# IOTBeev0_2.net
KiCad netlist of a schematic drawn in EAGLE
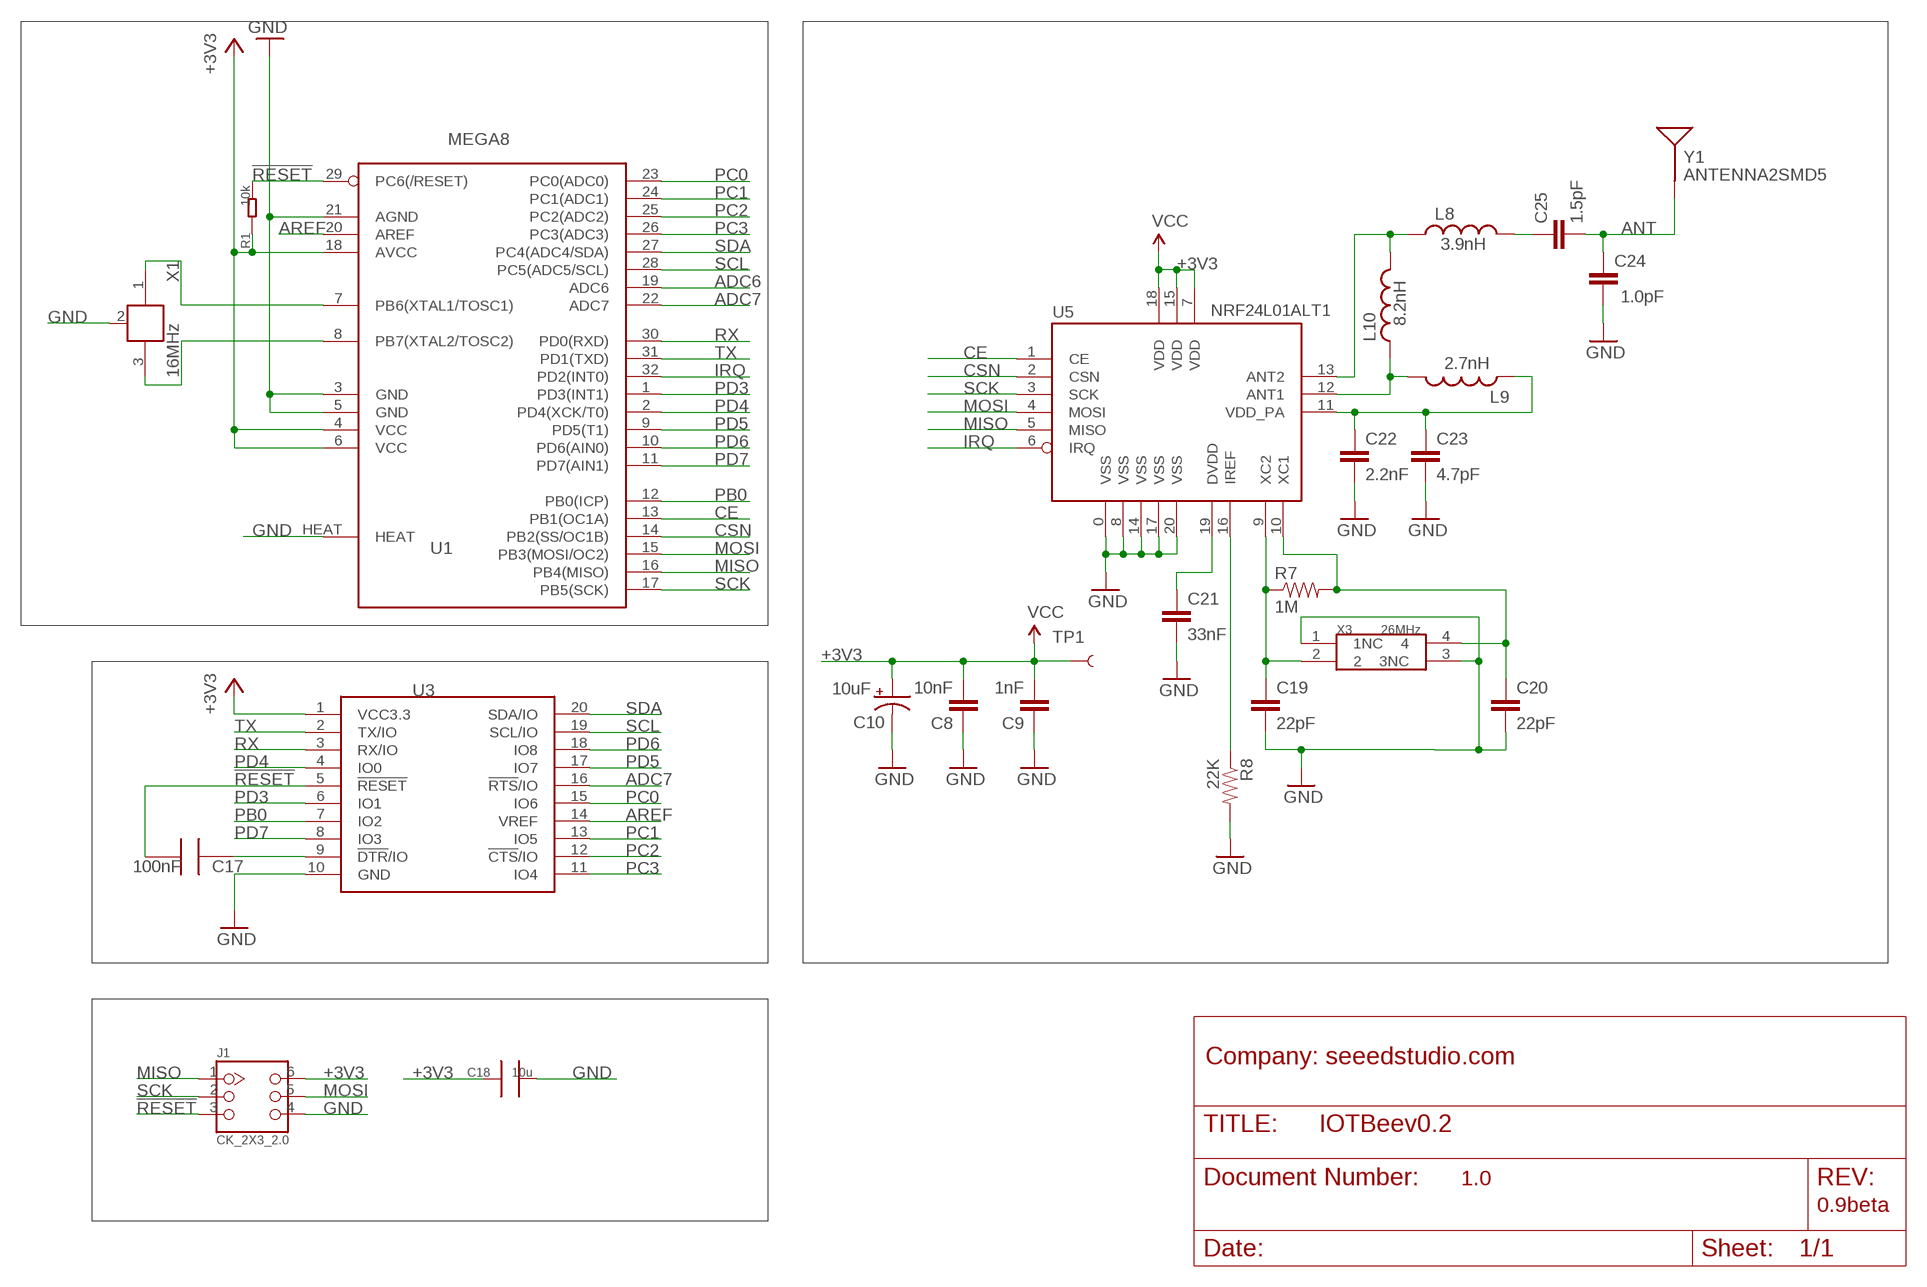
[diagram p0: schematic, sheet 1]

(export (version "E")
  (design (tool "Eeschema 10.0.6"))
  (components
    (comp (ref "C8")
      (value "10nF")
      (footprint "eagle-import:0402-CAP")
      (libsource (lib "eagle-import") (part "CAP0402-CAP"))
    )
    (comp (ref "C9")
      (value "1nF")
      (footprint "eagle-import:0402-CAP")
      (libsource (lib "eagle-import") (part "CAP0402-CAP"))
    )
    (comp (ref "C10")
      (value "10uF")
      (footprint "eagle-import:EIA3528")
      (libsource (lib "eagle-import") (part "CAP_POL3528"))
    )
    (comp (ref "C17")
      (value "100nF")
      (footprint "eagle-import:0603_S")
      (libsource (lib "eagle-import") (part "C0603_S"))
    )
    (comp (ref "C18")
      (value "10u")
      (footprint "eagle-import:0805")
      (libsource (lib "eagle-import") (part "C0805"))
    )
    (comp (ref "C19")
      (value "22pF")
      (footprint "eagle-import:0402-CAP")
      (libsource (lib "eagle-import") (part "CAP0402-CAP"))
    )
    (comp (ref "C20")
      (value "22pF")
      (footprint "eagle-import:0402-CAP")
      (libsource (lib "eagle-import") (part "CAP0402-CAP"))
    )
    (comp (ref "C21")
      (value "33nF")
      (footprint "eagle-import:0402-CAP")
      (libsource (lib "eagle-import") (part "CAP0402-CAP"))
    )
    (comp (ref "C22")
      (value "2.2nF")
      (footprint "eagle-import:0402-CAP")
      (libsource (lib "eagle-import") (part "CAP0402-CAP"))
    )
    (comp (ref "C23")
      (value "4.7pF")
      (footprint "eagle-import:0402-CAP")
      (libsource (lib "eagle-import") (part "CAP0402-CAP"))
    )
    (comp (ref "C24")
      (value "1.0pF")
      (footprint "eagle-import:0402-CAP")
      (libsource (lib "eagle-import") (part "CAP0402-CAP"))
    )
    (comp (ref "C25")
      (value "1.5pF")
      (footprint "eagle-import:0402-CAP")
      (libsource (lib "eagle-import") (part "CAP0402-CAP"))
    )
    (comp (ref "J1")
      (value "CK_2X3_2.0")
      (footprint "eagle-import:CK_2X3_2.0")
      (libsource (lib "eagle-import") (part "CK_2X3_2.0"))
    )
    (comp (ref "L8")
      (value "3.9nH")
      (footprint "eagle-import:C0402")
      (libsource (lib "eagle-import") (part "INDUCTOR0402"))
    )
    (comp (ref "L9")
      (value "2.7nH")
      (footprint "eagle-import:C0402")
      (libsource (lib "eagle-import") (part "INDUCTOR0402"))
    )
    (comp (ref "L10")
      (value "8.2nH")
      (footprint "eagle-import:C0402")
      (libsource (lib "eagle-import") (part "INDUCTOR0402"))
    )
    (comp (ref "R1")
      (value "10k")
      (footprint "eagle-import:0603_S")
      (libsource (lib "eagle-import") (part "R0603_S"))
    )
    (comp (ref "R7")
      (value "1M")
      (footprint "eagle-import:0402-RES")
      (libsource (lib "eagle-import") (part "RESISTOR0402-RES"))
    )
    (comp (ref "R8")
      (value "22K")
      (footprint "eagle-import:0402-RES")
      (libsource (lib "eagle-import") (part "RESISTOR0402-RES"))
    )
    (comp (ref "TP1")
      (value "TEST-POINT3X5")
      (footprint "eagle-import:PAD.03X.05")
      (libsource (lib "eagle-import") (part "TEST-POINT3X5"))
    )
    (comp (ref "U1")
      (value "MEGA8")
      (footprint "eagle-import:MLF32X")
      (libsource (lib "eagle-import") (part "MEGA8"))
    )
    (comp (ref "U3")
      (value "BEE-OPENBEE-BTSMD")
      (footprint "eagle-import:20P-SMD-2.0-BT")
      (libsource (lib "eagle-import") (part "BEE-OPENBEE-BTSMD"))
    )
    (comp (ref "U5")
      (value "NRF24L01ALT1")
      (footprint "eagle-import:QFN20_ALT1")
      (libsource (lib "eagle-import") (part "NRF24L01ALT1"))
    )
    (comp (ref "X1")
      (value "16MHz")
      (footprint "eagle-import:XTAL_3X2")
      (libsource (lib "eagle-import") (part "XTAL_NCVER"))
    )
    (comp (ref "X3")
      (value "26MHz")
      (footprint "eagle-import:X3225")
      (libsource (lib "eagle-import") (part "XTAL_SMD_3225"))
    )
    (comp (ref "Y1")
      (value "ANTENNA2SMD5")
      (footprint "eagle-import:ANTENNA-CHIP5")
      (libsource (lib "eagle-import") (part "ANTENNA2SMD5"))
    )
  )
  (nets
    (net (code "1") (name "+3V3") (class "Default")
      (node (ref "C10") (pin "A") (pinfunction "+_A") (pintype "passive"))
      (node (ref "C18") (pin "1") (pinfunction "1_1") (pintype "bidirectional"))
      (node (ref "C8") (pin "2") (pinfunction "2_2") (pintype "passive"))
      (node (ref "C9") (pin "2") (pinfunction "2_2") (pintype "passive"))
      (node (ref "J1") (pin "6") (pinfunction "P$6_6") (pintype "bidirectional"))
      (node (ref "R1") (pin "1") (pinfunction "1_1") (pintype "bidirectional"))
      (node (ref "TP1") (pin "P$1") (pinfunction "1_P$1") (pintype "bidirectional"))
      (node (ref "U1") (pin "18") (pinfunction "AVCC_18") (pintype "bidirectional"))
      (node (ref "U1") (pin "4") (pinfunction "VCC_4") (pintype "bidirectional"))
      (node (ref "U1") (pin "6") (pinfunction "VCC_6") (pintype "bidirectional"))
      (node (ref "U3") (pin "1") (pinfunction "VCC3.3_1") (pintype "bidirectional"))
      (node (ref "U5") (pin "15") (pinfunction "VDD_15") (pintype "power_in"))
      (node (ref "U5") (pin "18") (pinfunction "VDD_18") (pintype "power_in"))
      (node (ref "U5") (pin "7") (pinfunction "VDD_7") (pintype "power_in"))
    )
    (net (code "2") (name "/ADC6") (class "Default")
      (node (ref "U1") (pin "19") (pinfunction "ADC6_19") (pintype "bidirectional"))
    )
    (net (code "3") (name "/ADC7") (class "Default")
      (node (ref "U1") (pin "22") (pinfunction "ADC7_22") (pintype "bidirectional"))
      (node (ref "U3") (pin "16") (pinfunction "~{RTS}/IO_16") (pintype "bidirectional"))
    )
    (net (code "4") (name "/ANT") (class "Default")
      (node (ref "C24") (pin "2") (pinfunction "2_2") (pintype "passive"))
      (node (ref "C25") (pin "2") (pinfunction "2_2") (pintype "passive"))
      (node (ref "Y1") (pin "FEED") (pinfunction "SIGNAL_FEED") (pintype "bidirectional"))
    )
    (net (code "5") (name "/AREF") (class "Default")
      (node (ref "U1") (pin "20") (pinfunction "AREF_20") (pintype "bidirectional"))
      (node (ref "U3") (pin "14") (pinfunction "VREF_14") (pintype "bidirectional"))
    )
    (net (code "6") (name "/CE") (class "Default")
      (node (ref "U1") (pin "13") (pinfunction "PB1(OC1A)_13") (pintype "bidirectional"))
      (node (ref "U5") (pin "1") (pinfunction "CE_1") (pintype "input"))
    )
    (net (code "7") (name "/CSN") (class "Default")
      (node (ref "U1") (pin "14") (pinfunction "PB2(SS/OC1B)_14") (pintype "bidirectional"))
      (node (ref "U5") (pin "2") (pinfunction "CSN_2") (pintype "input"))
    )
    (net (code "8") (name "/IRQ") (class "Default")
      (node (ref "U1") (pin "32") (pinfunction "PD2(INT0)_32") (pintype "bidirectional"))
      (node (ref "U5") (pin "6") (pinfunction "IRQ_6") (pintype "output"))
    )
    (net (code "9") (name "/MISO") (class "Default")
      (node (ref "J1") (pin "1") (pinfunction "P$1_1") (pintype "bidirectional"))
      (node (ref "U1") (pin "16") (pinfunction "PB4(MISO)_16") (pintype "bidirectional"))
      (node (ref "U5") (pin "5") (pinfunction "MISO_5") (pintype "output"))
    )
    (net (code "10") (name "/MOSI") (class "Default")
      (node (ref "J1") (pin "5") (pinfunction "P$5_5") (pintype "bidirectional"))
      (node (ref "U1") (pin "15") (pinfunction "PB3(MOSI/OC2)_15") (pintype "bidirectional"))
      (node (ref "U5") (pin "4") (pinfunction "MOSI_4") (pintype "input"))
    )
    (net (code "11") (name "/PB0") (class "Default")
      (node (ref "U1") (pin "12") (pinfunction "PB0(ICP)_12") (pintype "bidirectional"))
      (node (ref "U3") (pin "7") (pinfunction "IO2_7") (pintype "bidirectional"))
    )
    (net (code "12") (name "/PC0") (class "Default")
      (node (ref "U1") (pin "23") (pinfunction "PC0(ADC0)_23") (pintype "bidirectional"))
      (node (ref "U3") (pin "15") (pinfunction "IO6_15") (pintype "bidirectional"))
    )
    (net (code "13") (name "/PC1") (class "Default")
      (node (ref "U1") (pin "24") (pinfunction "PC1(ADC1)_24") (pintype "bidirectional"))
      (node (ref "U3") (pin "13") (pinfunction "IO5_13") (pintype "bidirectional"))
    )
    (net (code "14") (name "/PC2") (class "Default")
      (node (ref "U1") (pin "25") (pinfunction "PC2(ADC2)_25") (pintype "bidirectional"))
      (node (ref "U3") (pin "12") (pinfunction "~{CTS}/IO_12") (pintype "bidirectional"))
    )
    (net (code "15") (name "/PC3") (class "Default")
      (node (ref "U1") (pin "26") (pinfunction "PC3(ADC3)_26") (pintype "bidirectional"))
      (node (ref "U3") (pin "11") (pinfunction "IO4_11") (pintype "bidirectional"))
    )
    (net (code "16") (name "/PD3") (class "Default")
      (node (ref "U1") (pin "1") (pinfunction "PD3(INT1)_1") (pintype "bidirectional"))
      (node (ref "U3") (pin "6") (pinfunction "IO1_6") (pintype "bidirectional"))
    )
    (net (code "17") (name "/PD4") (class "Default")
      (node (ref "U1") (pin "2") (pinfunction "PD4(XCK/T0)_2") (pintype "bidirectional"))
      (node (ref "U3") (pin "4") (pinfunction "IO0_4") (pintype "bidirectional"))
    )
    (net (code "18") (name "/PD5") (class "Default")
      (node (ref "U1") (pin "9") (pinfunction "PD5(T1)_9") (pintype "bidirectional"))
      (node (ref "U3") (pin "17") (pinfunction "IO7_17") (pintype "bidirectional"))
    )
    (net (code "19") (name "/PD6") (class "Default")
      (node (ref "U1") (pin "10") (pinfunction "PD6(AIN0)_10") (pintype "bidirectional"))
      (node (ref "U3") (pin "18") (pinfunction "IO8_18") (pintype "bidirectional"))
    )
    (net (code "20") (name "/PD7") (class "Default")
      (node (ref "U1") (pin "11") (pinfunction "PD7(AIN1)_11") (pintype "bidirectional"))
      (node (ref "U3") (pin "8") (pinfunction "IO3_8") (pintype "bidirectional"))
    )
    (net (code "21") (name "/RX") (class "Default")
      (node (ref "U1") (pin "30") (pinfunction "PD0(RXD)_30") (pintype "bidirectional"))
      (node (ref "U3") (pin "3") (pinfunction "RX/IO_3") (pintype "bidirectional"))
    )
    (net (code "22") (name "/SCK") (class "Default")
      (node (ref "J1") (pin "2") (pinfunction "P$2_2") (pintype "bidirectional"))
      (node (ref "U1") (pin "17") (pinfunction "PB5(SCK)_17") (pintype "bidirectional"))
      (node (ref "U5") (pin "3") (pinfunction "SCK_3") (pintype "input"))
    )
    (net (code "23") (name "/SCL") (class "Default")
      (node (ref "U1") (pin "28") (pinfunction "PC5(ADC5/SCL)_28") (pintype "bidirectional"))
      (node (ref "U3") (pin "19") (pinfunction "SCL/IO_19") (pintype "bidirectional"))
    )
    (net (code "24") (name "/SDA") (class "Default")
      (node (ref "U1") (pin "27") (pinfunction "PC4(ADC4/SDA)_27") (pintype "bidirectional"))
      (node (ref "U3") (pin "20") (pinfunction "SDA/IO_20") (pintype "bidirectional"))
    )
    (net (code "25") (name "/TX") (class "Default")
      (node (ref "U1") (pin "31") (pinfunction "PD1(TXD)_31") (pintype "bidirectional"))
      (node (ref "U3") (pin "2") (pinfunction "TX/IO_2") (pintype "bidirectional"))
    )
    (net (code "26") (name "/~{RESET}") (class "Default")
      (node (ref "C17") (pin "2") (pinfunction "2_2") (pintype "bidirectional"))
      (node (ref "J1") (pin "3") (pinfunction "P$3_3") (pintype "bidirectional"))
      (node (ref "R1") (pin "2") (pinfunction "2_2") (pintype "bidirectional"))
      (node (ref "U1") (pin "29") (pinfunction "PC6(/RESET)_29") (pintype "bidirectional"))
      (node (ref "U3") (pin "5") (pinfunction "~{RESET}_5") (pintype "bidirectional"))
    )
    (net (code "27") (name "GND") (class "Default")
      (node (ref "C10") (pin "C") (pinfunction "-_C") (pintype "passive"))
      (node (ref "C18") (pin "2") (pinfunction "2_2") (pintype "bidirectional"))
      (node (ref "C19") (pin "2") (pinfunction "2_2") (pintype "passive"))
      (node (ref "C20") (pin "2") (pinfunction "2_2") (pintype "passive"))
      (node (ref "C21") (pin "2") (pinfunction "2_2") (pintype "passive"))
      (node (ref "C22") (pin "2") (pinfunction "2_2") (pintype "passive"))
      (node (ref "C23") (pin "2") (pinfunction "2_2") (pintype "passive"))
      (node (ref "C24") (pin "1") (pinfunction "1_1") (pintype "passive"))
      (node (ref "C8") (pin "1") (pinfunction "1_1") (pintype "passive"))
      (node (ref "C9") (pin "1") (pinfunction "1_1") (pintype "passive"))
      (node (ref "J1") (pin "4") (pinfunction "P$4_4") (pintype "bidirectional"))
      (node (ref "R8") (pin "2") (pinfunction "2_2") (pintype "passive"))
      (node (ref "U1") (pin "21") (pinfunction "AGND_21") (pintype "bidirectional"))
      (node (ref "U1") (pin "3") (pinfunction "GND_3") (pintype "bidirectional"))
      (node (ref "U1") (pin "5") (pinfunction "GND_5") (pintype "bidirectional"))
      (node (ref "U1") (pin "HEAT") (pinfunction "HEAT_HEAT") (pintype "bidirectional"))
      (node (ref "U3") (pin "10") (pinfunction "GND_10") (pintype "bidirectional"))
      (node (ref "U5") (pin "0") (pinfunction "VSS_0") (pintype "power_in"))
      (node (ref "U5") (pin "14") (pinfunction "VSS_14") (pintype "power_in"))
      (node (ref "U5") (pin "17") (pinfunction "VSS_17") (pintype "power_in"))
      (node (ref "U5") (pin "20") (pinfunction "VSS_20") (pintype "power_in"))
      (node (ref "U5") (pin "8") (pinfunction "VSS_8") (pintype "power_in"))
      (node (ref "X1") (pin "2") (pinfunction "GND_2") (pintype "bidirectional"))
      (node (ref "X3") (pin "1") (pinfunction "1NC_1") (pintype "bidirectional"))
      (node (ref "X3") (pin "3") (pinfunction "3NC_3") (pintype "bidirectional"))
    )
    (net (code "28") (name "Net-(C25-Pad1)") (class "Default")
      (node (ref "C25") (pin "1") (pinfunction "1_1") (pintype "passive"))
      (node (ref "L8") (pin "2") (pinfunction "2_2") (pintype "passive"))
    )
    (net (code "29") (name "Net-(U1-PB6(XTAL1{slash}TOSC1))") (class "Default")
      (node (ref "U1") (pin "7") (pinfunction "PB6(XTAL1/TOSC1)_7") (pintype "bidirectional"))
      (node (ref "X1") (pin "1") (pinfunction "1_1") (pintype "bidirectional"))
    )
    (net (code "30") (name "Net-(U1-PB7(XTAL2{slash}TOSC2))") (class "Default")
      (node (ref "U1") (pin "8") (pinfunction "PB7(XTAL2/TOSC2)_8") (pintype "bidirectional"))
      (node (ref "X1") (pin "3") (pinfunction "2_3") (pintype "bidirectional"))
    )
    (net (code "31") (name "Net-(U3-~{DTR}{slash}IO)") (class "Default")
      (node (ref "C17") (pin "1") (pinfunction "1_1") (pintype "bidirectional"))
      (node (ref "U3") (pin "9") (pinfunction "~{DTR}/IO_9") (pintype "bidirectional"))
    )
    (net (code "32") (name "Net-(U5-ANT1)") (class "Default")
      (node (ref "L10") (pin "1") (pinfunction "1_1") (pintype "passive"))
      (node (ref "L9") (pin "2") (pinfunction "2_2") (pintype "passive"))
      (node (ref "U5") (pin "12") (pinfunction "ANT1_12") (pintype "output"))
    )
    (net (code "33") (name "Net-(U5-ANT2)") (class "Default")
      (node (ref "L10") (pin "2") (pinfunction "2_2") (pintype "passive"))
      (node (ref "L8") (pin "1") (pinfunction "1_1") (pintype "passive"))
      (node (ref "U5") (pin "13") (pinfunction "ANT2_13") (pintype "output"))
    )
    (net (code "34") (name "Net-(U5-DVDD)") (class "Default")
      (node (ref "C21") (pin "1") (pinfunction "1_1") (pintype "passive"))
      (node (ref "U5") (pin "19") (pinfunction "DVDD_19") (pintype "power_in"))
    )
    (net (code "35") (name "Net-(U5-IREF)") (class "Default")
      (node (ref "R8") (pin "1") (pinfunction "1_1") (pintype "passive"))
      (node (ref "U5") (pin "16") (pinfunction "IREF_16") (pintype "input"))
    )
    (net (code "36") (name "Net-(U5-VDD_PA)") (class "Default")
      (node (ref "C22") (pin "1") (pinfunction "1_1") (pintype "passive"))
      (node (ref "C23") (pin "1") (pinfunction "1_1") (pintype "passive"))
      (node (ref "L9") (pin "1") (pinfunction "1_1") (pintype "passive"))
      (node (ref "U5") (pin "11") (pinfunction "VDD_PA_11") (pintype "power_in"))
    )
    (net (code "37") (name "Net-(U5-XC1)") (class "Default")
      (node (ref "C20") (pin "1") (pinfunction "1_1") (pintype "passive"))
      (node (ref "R7") (pin "2") (pinfunction "2_2") (pintype "passive"))
      (node (ref "U5") (pin "10") (pinfunction "XC1_10") (pintype "input"))
      (node (ref "X3") (pin "4") (pinfunction "4_4") (pintype "bidirectional"))
    )
    (net (code "38") (name "Net-(U5-XC2)") (class "Default")
      (node (ref "C19") (pin "1") (pinfunction "1_1") (pintype "passive"))
      (node (ref "R7") (pin "1") (pinfunction "1_1") (pintype "passive"))
      (node (ref "U5") (pin "9") (pinfunction "XC2_9") (pintype "input"))
      (node (ref "X3") (pin "2") (pinfunction "2_2") (pintype "bidirectional"))
    )
  )
)
